# motor.net
KiCad netlist of a schematic drawn in Altium Designer
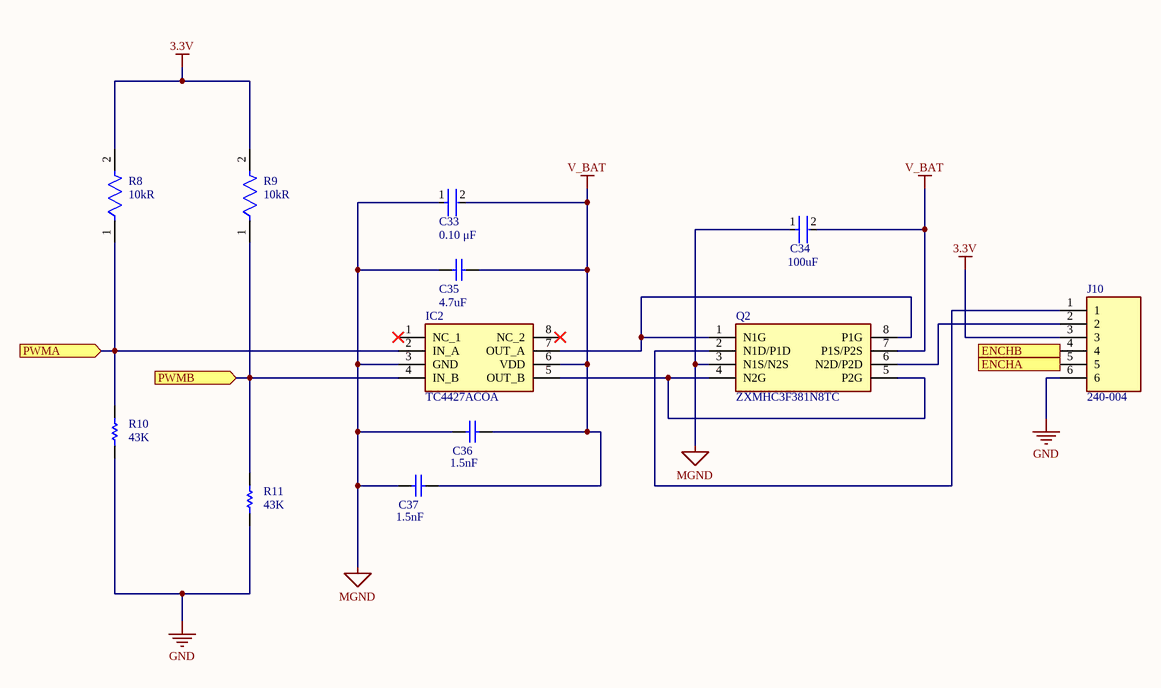
[diagram p0: motor.SchDoc]

(export (version "E")
  (design (tool "Eeschema 10.0.6"))
  (components
    (comp (ref "C33")
      (value "0.10 μF")
      (footprint "FP-C0805C-DN-MFG")
      (description "CAP CER 0.1UF 10V 5% X7R 0805")
      (fields (field (name "MANUFACTURER") "KEMET") (field (name "TOLERANCE") "0.05"))
      (libsource (lib "Altium Content Vault") (part "b4654b650e69147ec39a6b967a45e02"))
    )
    (comp (ref "C34")
      (value "C1206C107M9PACTU")
      (footprint "FP-C1206C-EH-MFG")
      (description "CAP CER 100UF 6.3V X5R 1206")
      (fields
        (field (name "TOLERANCE") "2%")
        (field (name "CAPACITANCE") "100uF")
        (field (name "VOLTAGE") "6.3V")
      )
      (libsource (lib "Altium Content Vault") (part "02cd4be3c70576c341d710602a673aa"))
    )
    (comp (ref "C35")
      (value "4.7uF")
      (footprint "CAPC2013X145X50NL20T25")
      (fields (field (name "PART NUMBER") "C0805C475M3PACTU") (field (name "MANUFACTURER") "Kemet"))
      (libsource (lib "Altium Content Vault") (part "CAP"))
    )
    (comp (ref "C36")
      (value "1.5nF")
      (footprint "CAPC2013X94X50NL20T25")
      (fields
        (field (name "MANUFACTURER") "AVX Interconnect / Elco")
        (field (name "PART NUMBER") "08051C152KAT2A")
      )
      (libsource (lib "Altium Content Vault") (part "CAP"))
    )
    (comp (ref "C37")
      (value "1.5nF")
      (footprint "CAPC2013X94X50NL20T25")
      (fields
        (field (name "MANUFACTURER") "AVX Interconnect / Elco")
        (field (name "PART NUMBER") "08051C152KAT2A")
      )
      (libsource (lib "Altium Content Vault") (part "CAP"))
    )
    (comp (ref "IC2")
      (value "TC4427ACOA")
      (footprint "SamacSys:SOIC127P600X175-8N")
      (description "Integrated Circuit")
      (fields (field (name "MOUSER PART NUMBER") "579-TC4427ACOA"))
      (libsource (lib "*") (part "TC4427ACOA"))
    )
    (comp (ref "J10")
      (value "240-004")
      (footprint "SamacSys:HDRV6W64P0X254_1X6_1524X254X909P")
      (description "Connector")
      (libsource (lib "*") (part "240-004"))
    )
    (comp (ref "Q2")
      (value "ZXMHC3F381N8TC")
      (footprint "SamacSys:SOIC127P600X170-8N")
      (description "MOSFET (N-Channel)")
      (fields (field (name "MOUSER PART NUMBER") "522-ZXMHC3F381N8TC"))
      (libsource (lib "*") (part "ZXMHC3F381N8TC"))
    )
    (comp (ref "R8")
      (value "ERA-3AEB103V")
      (footprint "FP-ERA3A-IPC_C")
      (description "RES SMD 10K OHM 0.1% 1/10W 0603")
      (fields (field (name "RESISTANCE") "10kR") (field (name "TOLERANCE") "0.1%"))
      (libsource (lib "Altium Content Vault") (part "4e5f8b3dd332802e91518312df5df73"))
    )
    (comp (ref "R9")
      (value "ERA-3AEB103V")
      (footprint "FP-ERA3A-IPC_C")
      (description "RES SMD 10K OHM 0.1% 1/10W 0603")
      (fields (field (name "RESISTANCE") "10kR") (field (name "TOLERANCE") "0.1%"))
      (libsource (lib "Altium Content Vault") (part "4e5f8b3dd332802e91518312df5df73"))
    )
    (comp (ref "R10")
      (value "43K")
      (footprint "RESC1608X55X30ML20T20")
      (fields (field (name "PART NUMBER") "ERA3AEB433V") (field (name "MANUFACTURER") "Panasonic"))
      (libsource (lib "Altium Content Vault") (part "RES"))
    )
    (comp (ref "R11")
      (value "43K")
      (footprint "RESC1608X55X30ML20T20")
      (fields (field (name "PART NUMBER") "ERA3AEB433V") (field (name "MANUFACTURER") "Panasonic"))
      (libsource (lib "Altium Content Vault") (part "RES"))
    )
  )
  (nets
    (net (code "1") (name "/ENCHA") (class "Default")
      (node (ref "J10") (pin "5") (pinfunction "5_5") (pintype "passive"))
    )
    (net (code "2") (name "/ENCHB") (class "Default")
      (node (ref "J10") (pin "4") (pinfunction "4_4") (pintype "passive"))
    )
    (net (code "3") (name "/PWMA") (class "Default")
      (node (ref "IC2") (pin "2") (pinfunction "IN_A_2") (pintype "passive"))
      (node (ref "R10") (pin "2") (pinfunction "2_2") (pintype "passive"))
      (node (ref "R8") (pin "1") (pinfunction "1_1") (pintype "passive"))
    )
    (net (code "4") (name "/PWMB") (class "Default")
      (node (ref "IC2") (pin "4") (pinfunction "IN_B_4") (pintype "passive"))
      (node (ref "R11") (pin "2") (pinfunction "2_2") (pintype "passive"))
      (node (ref "R9") (pin "1") (pinfunction "1_1") (pintype "passive"))
    )
    (net (code "5") (name "3.3V") (class "Default")
      (node (ref "J10") (pin "3") (pinfunction "3_3") (pintype "passive"))
      (node (ref "R8") (pin "2") (pinfunction "2_2") (pintype "passive"))
      (node (ref "R9") (pin "2") (pinfunction "2_2") (pintype "passive"))
    )
    (net (code "6") (name "GND") (class "Default")
      (node (ref "J10") (pin "6") (pinfunction "6_6") (pintype "passive"))
      (node (ref "R10") (pin "1") (pinfunction "1_1") (pintype "passive"))
      (node (ref "R11") (pin "1") (pinfunction "1_1") (pintype "passive"))
    )
    (net (code "7") (name "MGND") (class "Default")
      (node (ref "C33") (pin "1") (pinfunction "1_1") (pintype "passive"))
      (node (ref "C34") (pin "1") (pinfunction "1_1") (pintype "passive"))
      (node (ref "C35") (pin "1") (pinfunction "1_1") (pintype "passive"))
      (node (ref "C36") (pin "1") (pinfunction "1_1") (pintype "passive"))
      (node (ref "C37") (pin "1") (pinfunction "1_1") (pintype "passive"))
      (node (ref "IC2") (pin "3") (pinfunction "GND_3") (pintype "passive"))
      (node (ref "Q2") (pin "3") (pinfunction "N1S/N2S_3") (pintype "passive"))
    )
    (net (code "8") (name "Net-(IC2-OUT_A)") (class "Default")
      (node (ref "IC2") (pin "7") (pinfunction "OUT_A_7") (pintype "passive"))
      (node (ref "Q2") (pin "1") (pinfunction "N1G_1") (pintype "passive"))
      (node (ref "Q2") (pin "8") (pinfunction "P1G_8") (pintype "passive"))
    )
    (net (code "9") (name "Net-(IC2-OUT_B)") (class "Default")
      (node (ref "IC2") (pin "5") (pinfunction "OUT_B_5") (pintype "passive"))
      (node (ref "Q2") (pin "4") (pinfunction "N2G_4") (pintype "passive"))
      (node (ref "Q2") (pin "5") (pinfunction "P2G_5") (pintype "passive"))
    )
    (net (code "10") (name "Net-(Q2-N1D{slash}P1D)") (class "Default")
      (node (ref "J10") (pin "1") (pinfunction "1_1") (pintype "passive"))
      (node (ref "Q2") (pin "2") (pinfunction "N1D/P1D_2") (pintype "passive"))
    )
    (net (code "11") (name "Net-(Q2-N2D{slash}P2D)") (class "Default")
      (node (ref "J10") (pin "2") (pinfunction "2_2") (pintype "passive"))
      (node (ref "Q2") (pin "6") (pinfunction "N2D/P2D_6") (pintype "passive"))
    )
    (net (code "12") (name "V_BAT") (class "Default")
      (node (ref "C33") (pin "2") (pinfunction "2_2") (pintype "passive"))
      (node (ref "C34") (pin "2") (pinfunction "2_2") (pintype "passive"))
      (node (ref "C35") (pin "2") (pinfunction "2_2") (pintype "passive"))
      (node (ref "C36") (pin "2") (pinfunction "2_2") (pintype "passive"))
      (node (ref "C37") (pin "2") (pinfunction "2_2") (pintype "passive"))
      (node (ref "IC2") (pin "6") (pinfunction "VDD_6") (pintype "passive"))
      (node (ref "Q2") (pin "7") (pinfunction "P1S/P2S_7") (pintype "passive"))
    )
    (net (code "13") (name "unconnected-(IC2-NC_1-Pad1)") (class "Default")
      (node (ref "IC2") (pin "1") (pinfunction "NC_1_1") (pintype "passive+no_connect"))
    )
    (net (code "14") (name "unconnected-(IC2-NC_2-Pad8)") (class "Default")
      (node (ref "IC2") (pin "8") (pinfunction "NC_2_8") (pintype "passive+no_connect"))
    )
  )
)
